# paste_injector.net
KiCad netlist of a schematic drawn in EAGLE
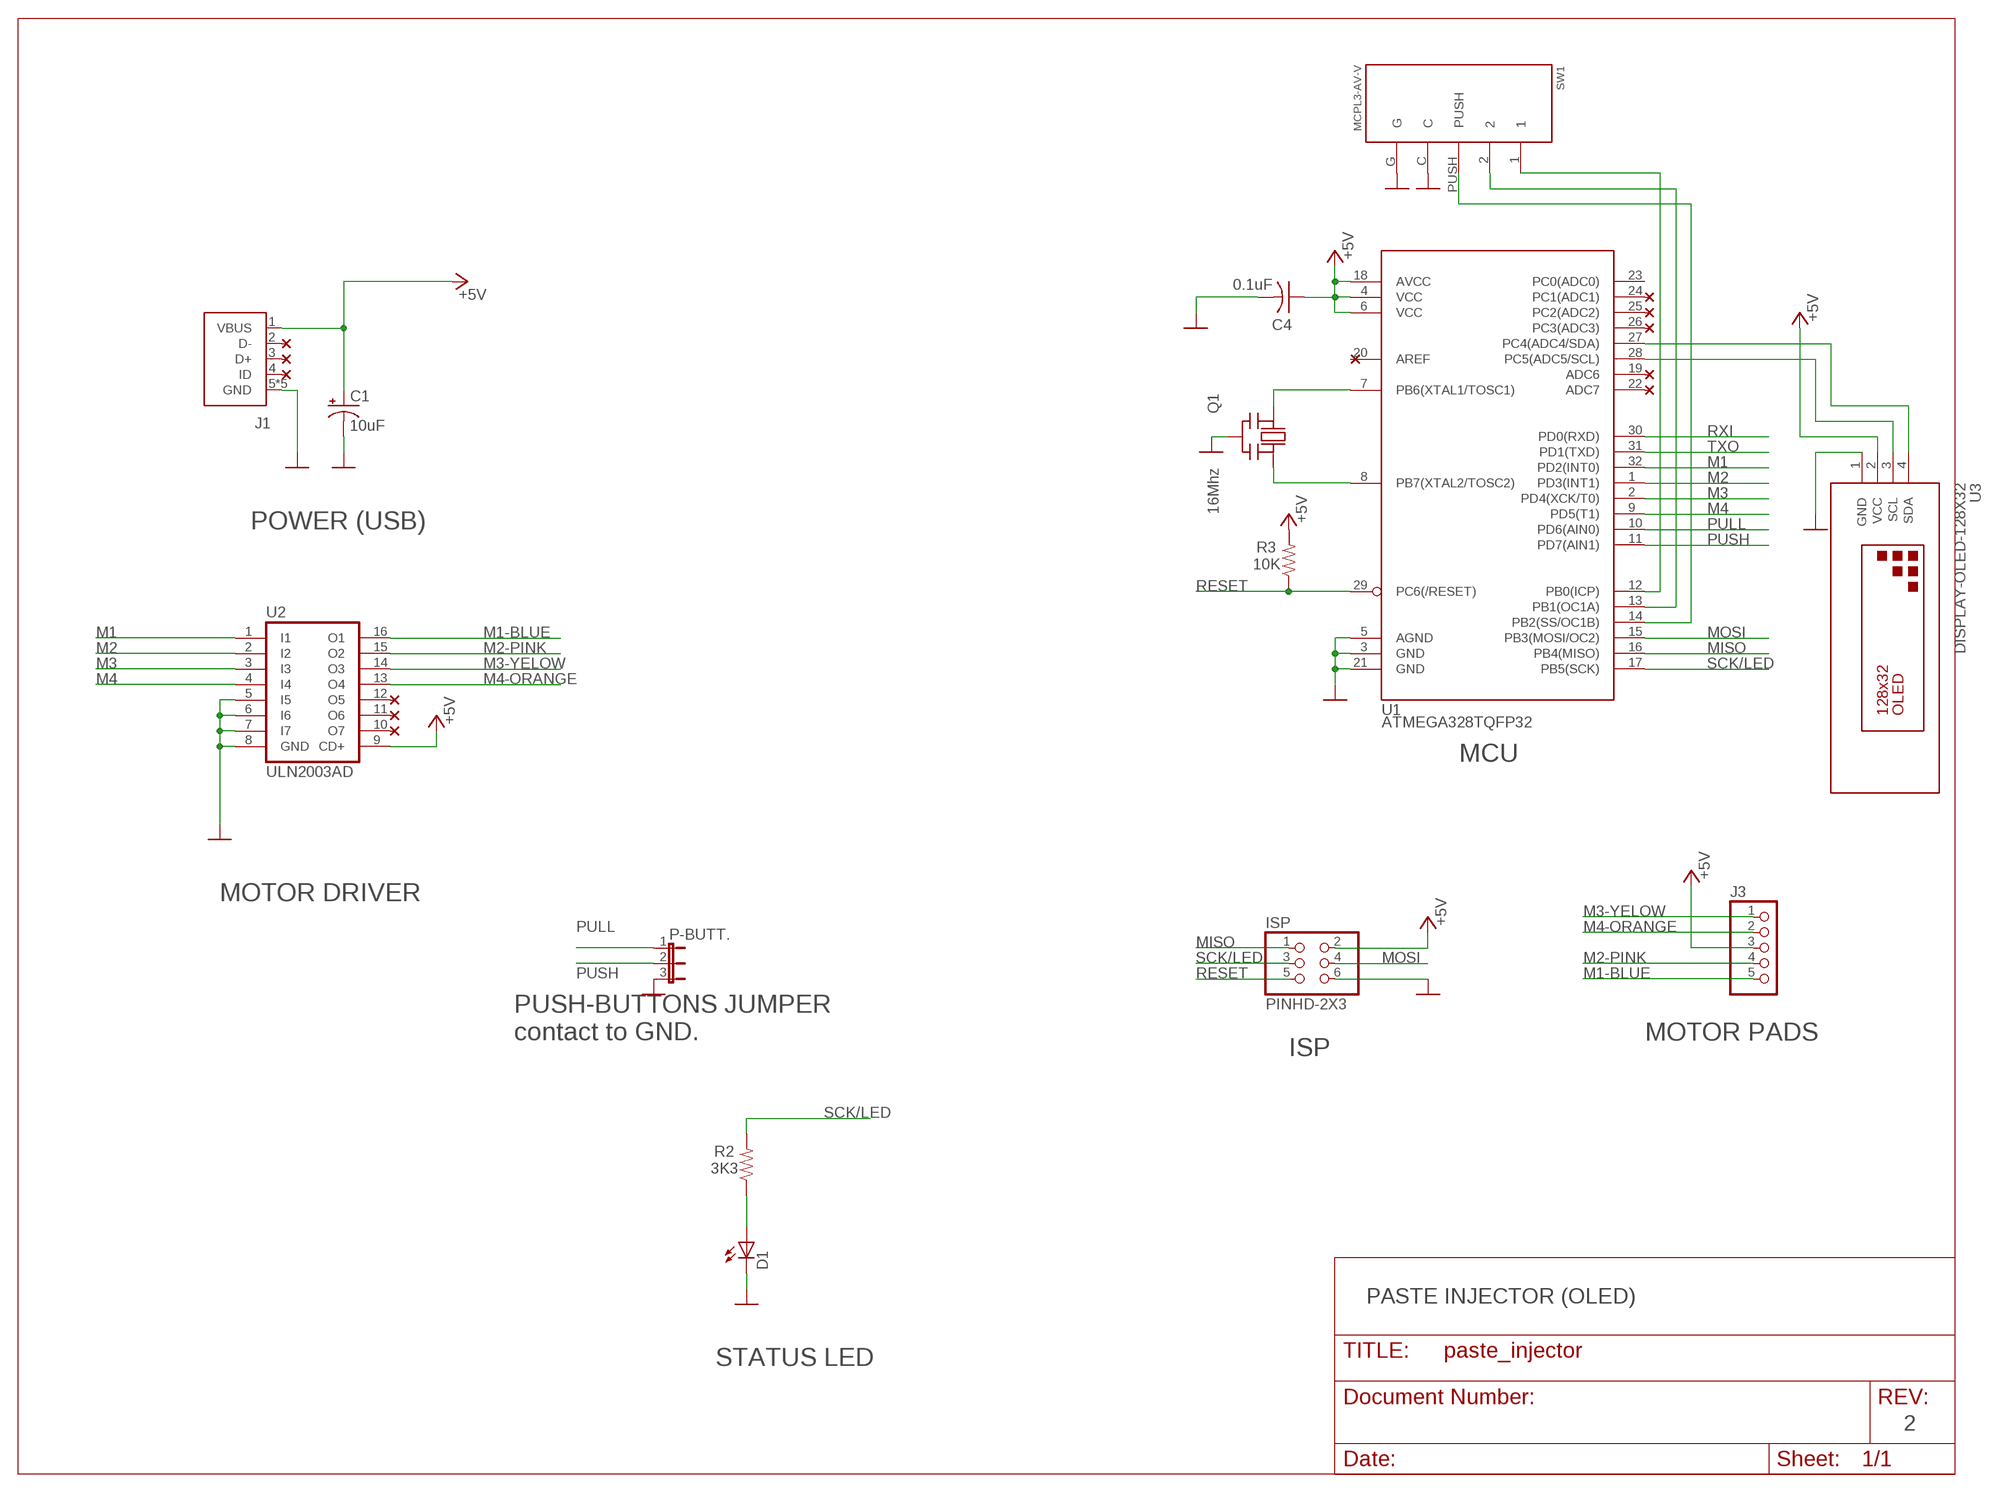
[diagram p0: schematic, sheet 1]

(export (version "E")
  (design (tool "Eeschema 10.0.6"))
  (components
    (comp (ref "C1")
      (value "10uF")
      (footprint "eagle-import:A_3216-18R")
      (libsource (lib "eagle-import") (part "CPOL-USA/3216-18R"))
    )
    (comp (ref "C4")
      (value "0.1uF")
      (footprint "eagle-import:C0603")
      (libsource (lib "eagle-import") (part "CAP-C0603"))
    )
    (comp (ref "D1")
      (value "LED")
      (footprint "eagle-import:LED0603")
      (libsource (lib "eagle-import") (part "LED"))
    )
    (comp (ref "ISP")
      (value "PINHD-2X3")
      (footprint "eagle-import:2X03")
      (libsource (lib "eagle-import") (part "PINHD-2X3"))
    )
    (comp (ref "J1")
      (value "USB")
      (footprint "eagle-import:USB-MICRO-ZX62RD-AB-5P8")
      (libsource (lib "eagle-import") (part "USB"))
    )
    (comp (ref "J3")
      (value "PINHD-1X5")
      (footprint "eagle-import:1X05")
      (libsource (lib "eagle-import") (part "PINHD-1X5"))
    )
    (comp (ref "P-BUTT.")
      (value "JP2E")
      (footprint "eagle-import:JP2")
      (libsource (lib "eagle-import") (part "JP2E"))
    )
    (comp (ref "Q1")
      (value "16Mhz")
      (footprint "eagle-import:CSTCR-G")
      (libsource (lib "eagle-import") (part "CERMOSCILL-CSTCRG"))
    )
    (comp (ref "R2")
      (value "3K3")
      (footprint "eagle-import:R0603")
      (libsource (lib "eagle-import") (part "RES-R0603"))
    )
    (comp (ref "R3")
      (value "10K")
      (footprint "eagle-import:R0603")
      (libsource (lib "eagle-import") (part "RES-R0603"))
    )
    (comp (ref "SW1")
      (value "MCPL3-AV-V")
      (footprint "eagle-import:MCPL3-AC-V")
      (libsource (lib "eagle-import") (part "MCPL3-AV-V"))
    )
    (comp (ref "U1")
      (value "ATMEGA328TQFP32")
      (footprint "eagle-import:TQFP32-08")
      (libsource (lib "eagle-import") (part "ATMEGA328TQFP32"))
    )
    (comp (ref "U2")
      (value "ULN2003AD")
      (footprint "eagle-import:SO16")
      (libsource (lib "eagle-import") (part "ULN2003AD"))
    )
    (comp (ref "U3")
      (value "DISPLAY-OLED-128X32")
      (footprint "eagle-import:DISPLAY-OLED-128X32")
      (libsource (lib "eagle-import") (part "DISPLAY-OLED-128X32"))
    )
  )
  (nets
    (net (code "1") (name "+5V") (class "Default")
      (node (ref "C1") (pin "+") (pinfunction "+_+") (pintype "passive"))
      (node (ref "C4") (pin "1") (pinfunction "1_1") (pintype "passive"))
      (node (ref "ISP") (pin "2") (pinfunction "2_2") (pintype "passive"))
      (node (ref "J1") (pin "1") (pinfunction "VBUS_1") (pintype "bidirectional"))
      (node (ref "J3") (pin "3") (pinfunction "3_3") (pintype "passive"))
      (node (ref "R3") (pin "2") (pinfunction "2_2") (pintype "passive"))
      (node (ref "U1") (pin "18") (pinfunction "AVCC_18") (pintype "power_in"))
      (node (ref "U1") (pin "4") (pinfunction "VCC_4") (pintype "power_in"))
      (node (ref "U1") (pin "6") (pinfunction "VCC_6") (pintype "power_in"))
      (node (ref "U2") (pin "9") (pinfunction "CD+_9") (pintype "passive"))
      (node (ref "U3") (pin "2") (pinfunction "VCC_2") (pintype "power_in"))
    )
    (net (code "2") (name "/AREF") (class "Default")
      (node (ref "U1") (pin "20") (pinfunction "AREF_20") (pintype "power_in"))
    )
    (net (code "3") (name "/M1") (class "Default")
      (node (ref "U1") (pin "32") (pinfunction "PD2(INT0)_32") (pintype "bidirectional"))
      (node (ref "U2") (pin "1") (pinfunction "I1_1") (pintype "input"))
    )
    (net (code "4") (name "/M1-BLUE") (class "Default")
      (node (ref "J3") (pin "5") (pinfunction "5_5") (pintype "passive"))
      (node (ref "U2") (pin "16") (pinfunction "O1_16") (pintype "open_collector"))
    )
    (net (code "5") (name "/M2") (class "Default")
      (node (ref "U1") (pin "1") (pinfunction "PD3(INT1)_1") (pintype "bidirectional"))
      (node (ref "U2") (pin "2") (pinfunction "I2_2") (pintype "input"))
    )
    (net (code "6") (name "/M2-PINK") (class "Default")
      (node (ref "J3") (pin "4") (pinfunction "4_4") (pintype "passive"))
      (node (ref "U2") (pin "15") (pinfunction "O2_15") (pintype "open_collector"))
    )
    (net (code "7") (name "/M3") (class "Default")
      (node (ref "U1") (pin "2") (pinfunction "PD4(XCK/T0)_2") (pintype "bidirectional"))
      (node (ref "U2") (pin "3") (pinfunction "I3_3") (pintype "input"))
    )
    (net (code "8") (name "/M3-YELOW") (class "Default")
      (node (ref "J3") (pin "1") (pinfunction "1_1") (pintype "passive"))
      (node (ref "U2") (pin "14") (pinfunction "O3_14") (pintype "open_collector"))
    )
    (net (code "9") (name "/M4") (class "Default")
      (node (ref "U1") (pin "9") (pinfunction "PD5(T1)_9") (pintype "bidirectional"))
      (node (ref "U2") (pin "4") (pinfunction "I4_4") (pintype "input"))
    )
    (net (code "10") (name "/M4-ORANGE") (class "Default")
      (node (ref "J3") (pin "2") (pinfunction "2_2") (pintype "passive"))
      (node (ref "U2") (pin "13") (pinfunction "O4_13") (pintype "open_collector"))
    )
    (net (code "11") (name "/MISO") (class "Default")
      (node (ref "ISP") (pin "1") (pinfunction "1_1") (pintype "passive"))
      (node (ref "U1") (pin "16") (pinfunction "PB4(MISO)_16") (pintype "bidirectional"))
    )
    (net (code "12") (name "/MOSI") (class "Default")
      (node (ref "ISP") (pin "4") (pinfunction "4_4") (pintype "passive"))
      (node (ref "U1") (pin "15") (pinfunction "PB3(MOSI/OC2)_15") (pintype "bidirectional"))
    )
    (net (code "13") (name "/PULL") (class "Default")
      (node (ref "P-BUTT.") (pin "1") (pinfunction "1_1") (pintype "passive"))
      (node (ref "U1") (pin "10") (pinfunction "PD6(AIN0)_10") (pintype "bidirectional"))
    )
    (net (code "14") (name "/PUSH") (class "Default")
      (node (ref "P-BUTT.") (pin "2") (pinfunction "2_2") (pintype "passive"))
      (node (ref "U1") (pin "11") (pinfunction "PD7(AIN1)_11") (pintype "bidirectional"))
    )
    (net (code "15") (name "/RESET") (class "Default")
      (node (ref "ISP") (pin "5") (pinfunction "5_5") (pintype "passive"))
      (node (ref "R3") (pin "1") (pinfunction "1_1") (pintype "passive"))
      (node (ref "U1") (pin "29") (pinfunction "PC6(/RESET)_29") (pintype "bidirectional"))
    )
    (net (code "16") (name "/RXI") (class "Default")
      (node (ref "U1") (pin "30") (pinfunction "PD0(RXD)_30") (pintype "bidirectional"))
    )
    (net (code "17") (name "/SCK{slash}LED") (class "Default")
      (node (ref "ISP") (pin "3") (pinfunction "3_3") (pintype "passive"))
      (node (ref "R2") (pin "2") (pinfunction "2_2") (pintype "passive"))
      (node (ref "U1") (pin "17") (pinfunction "PB5(SCK)_17") (pintype "bidirectional"))
    )
    (net (code "18") (name "/TXO") (class "Default")
      (node (ref "U1") (pin "31") (pinfunction "PD1(TXD)_31") (pintype "bidirectional"))
    )
    (net (code "19") (name "GND") (class "Default")
      (node (ref "C1") (pin "-") (pinfunction "-_-") (pintype "passive"))
      (node (ref "C4") (pin "2") (pinfunction "2_2") (pintype "passive"))
      (node (ref "D1") (pin "C") (pinfunction "C_C") (pintype "passive"))
      (node (ref "ISP") (pin "6") (pinfunction "6_6") (pintype "passive"))
      (node (ref "J1") (pin "5") (pinfunction "GND_5") (pintype "bidirectional"))
      (node (ref "J1") (pin "A") (pinfunction "GND_A") (pintype "bidirectional"))
      (node (ref "J1") (pin "B") (pinfunction "GND_B") (pintype "bidirectional"))
      (node (ref "J1") (pin "C") (pinfunction "GND_C") (pintype "bidirectional"))
      (node (ref "J1") (pin "D") (pinfunction "GND_D") (pintype "bidirectional"))
      (node (ref "P-BUTT.") (pin "3") (pinfunction "3_3") (pintype "passive"))
      (node (ref "Q1") (pin "2") (pinfunction "GND_2") (pintype "bidirectional"))
      (node (ref "SW1") (pin "C") (pinfunction "C_C") (pintype "bidirectional"))
      (node (ref "SW1") (pin "G") (pinfunction "G_G") (pintype "bidirectional"))
      (node (ref "U1") (pin "21") (pinfunction "GND_21") (pintype "power_in"))
      (node (ref "U1") (pin "3") (pinfunction "GND_3") (pintype "power_in"))
      (node (ref "U1") (pin "5") (pinfunction "AGND_5") (pintype "power_in"))
      (node (ref "U2") (pin "5") (pinfunction "I5_5") (pintype "input"))
      (node (ref "U2") (pin "6") (pinfunction "I6_6") (pintype "input"))
      (node (ref "U2") (pin "7") (pinfunction "I7_7") (pintype "input"))
      (node (ref "U2") (pin "8") (pinfunction "GND_8") (pintype "power_in"))
      (node (ref "U3") (pin "1") (pinfunction "GND_1") (pintype "power_in"))
    )
    (net (code "20") (name "Net-(D1-PadA)") (class "Default")
      (node (ref "D1") (pin "A") (pinfunction "A_A") (pintype "passive"))
      (node (ref "R2") (pin "1") (pinfunction "1_1") (pintype "passive"))
    )
    (net (code "21") (name "Net-(Q1-IN)") (class "Default")
      (node (ref "Q1") (pin "1") (pinfunction "IN_1") (pintype "bidirectional"))
      (node (ref "U1") (pin "7") (pinfunction "PB6(XTAL1/TOSC1)_7") (pintype "bidirectional"))
    )
    (net (code "22") (name "Net-(Q1-OUT)") (class "Default")
      (node (ref "Q1") (pin "3") (pinfunction "OUT_3") (pintype "bidirectional"))
      (node (ref "U1") (pin "8") (pinfunction "PB7(XTAL2/TOSC2)_8") (pintype "bidirectional"))
    )
    (net (code "23") (name "Net-(U1-PB0(ICP))") (class "Default")
      (node (ref "SW1") (pin "1") (pinfunction "1_1") (pintype "bidirectional"))
      (node (ref "U1") (pin "12") (pinfunction "PB0(ICP)_12") (pintype "bidirectional"))
    )
    (net (code "24") (name "Net-(U1-PB1(OC1A))") (class "Default")
      (node (ref "SW1") (pin "2") (pinfunction "2_2") (pintype "bidirectional"))
      (node (ref "U1") (pin "13") (pinfunction "PB1(OC1A)_13") (pintype "bidirectional"))
    )
    (net (code "25") (name "Net-(U1-PB2(SS{slash}OC1B))") (class "Default")
      (node (ref "SW1") (pin "PUSH") (pinfunction "PUSH_PUSH") (pintype "bidirectional"))
      (node (ref "U1") (pin "14") (pinfunction "PB2(SS/OC1B)_14") (pintype "bidirectional"))
    )
    (net (code "26") (name "Net-(U1-PC4(ADC4{slash}SDA))") (class "Default")
      (node (ref "U1") (pin "27") (pinfunction "PC4(ADC4/SDA)_27") (pintype "bidirectional"))
      (node (ref "U3") (pin "4") (pinfunction "SDA_4") (pintype "bidirectional"))
    )
    (net (code "27") (name "Net-(U1-PC5(ADC5{slash}SCL))") (class "Default")
      (node (ref "U1") (pin "28") (pinfunction "PC5(ADC5/SCL)_28") (pintype "bidirectional"))
      (node (ref "U3") (pin "3") (pinfunction "SCL_3") (pintype "bidirectional"))
    )
    (net (code "28") (name "unconnected-(J1-D+-Pad3)") (class "Default")
      (node (ref "J1") (pin "3") (pinfunction "D+_3") (pintype "bidirectional"))
    )
    (net (code "29") (name "unconnected-(J1-D--Pad2)") (class "Default")
      (node (ref "J1") (pin "2") (pinfunction "D-_2") (pintype "bidirectional"))
    )
    (net (code "30") (name "unconnected-(J1-ID-Pad4)") (class "Default")
      (node (ref "J1") (pin "4") (pinfunction "ID_4") (pintype "bidirectional"))
    )
    (net (code "31") (name "unconnected-(U1-ADC6-Pad19)") (class "Default")
      (node (ref "U1") (pin "19") (pinfunction "ADC6_19") (pintype "bidirectional"))
    )
    (net (code "32") (name "unconnected-(U1-ADC7-Pad22)") (class "Default")
      (node (ref "U1") (pin "22") (pinfunction "ADC7_22") (pintype "bidirectional"))
    )
    (net (code "33") (name "unconnected-(U1-PC0(ADC0)-Pad23)") (class "Default")
      (node (ref "U1") (pin "23") (pinfunction "PC0(ADC0)_23") (pintype "bidirectional"))
    )
    (net (code "34") (name "unconnected-(U1-PC1(ADC1)-Pad24)") (class "Default")
      (node (ref "U1") (pin "24") (pinfunction "PC1(ADC1)_24") (pintype "bidirectional"))
    )
    (net (code "35") (name "unconnected-(U1-PC2(ADC2)-Pad25)") (class "Default")
      (node (ref "U1") (pin "25") (pinfunction "PC2(ADC2)_25") (pintype "bidirectional"))
    )
    (net (code "36") (name "unconnected-(U1-PC3(ADC3)-Pad26)") (class "Default")
      (node (ref "U1") (pin "26") (pinfunction "PC3(ADC3)_26") (pintype "bidirectional"))
    )
    (net (code "37") (name "unconnected-(U2-O5-Pad12)") (class "Default")
      (node (ref "U2") (pin "12") (pinfunction "O5_12") (pintype "open_collector"))
    )
    (net (code "38") (name "unconnected-(U2-O6-Pad11)") (class "Default")
      (node (ref "U2") (pin "11") (pinfunction "O6_11") (pintype "open_collector"))
    )
    (net (code "39") (name "unconnected-(U2-O7-Pad10)") (class "Default")
      (node (ref "U2") (pin "10") (pinfunction "O7_10") (pintype "open_collector"))
    )
  )
)
